# MPU-9250.net
KiCad netlist of a schematic drawn in Altium Designer
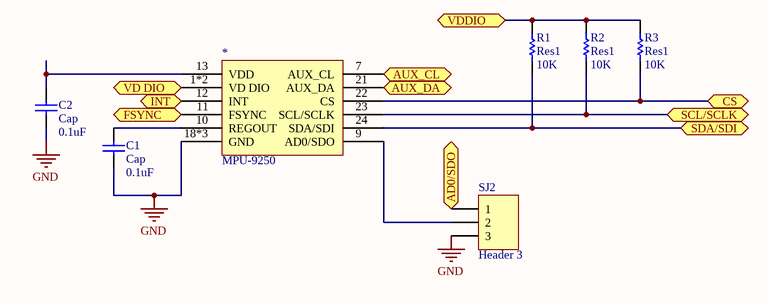
[diagram p0: MPU-9250.SchDoc]

(export (version "E")
  (design (tool "Eeschema 10.0.6"))
  (components
    (comp (ref "*") (value "MPU-9250") (libsource (lib "MPU-9250") (part "Component_1")))
    (comp (ref "C1")
      (value "Cap")
      (footprint "RAD-0.3")
      (description "Capacitor")
      (fields (field (name "ALTIUM_VALUE") "0.1uF") (field (name "PUBLISHER") "Altium Limited"))
      (libsource (lib "Miscellaneous Devices") (part "Cap"))
    )
    (comp (ref "C2")
      (value "Cap")
      (footprint "RAD-0.3")
      (description "Capacitor")
      (fields (field (name "ALTIUM_VALUE") "0.1uF") (field (name "PUBLISHER") "Altium Limited"))
      (libsource (lib "Miscellaneous Devices") (part "Cap"))
    )
    (comp (ref "R1")
      (value "Res1")
      (footprint "AXIAL-0.3")
      (description "Resistor")
      (fields (field (name "ALTIUM_VALUE") "10K") (field (name "PUBLISHER") "Altium Limited"))
      (libsource (lib "Miscellaneous Devices") (part "Res1"))
    )
    (comp (ref "R2")
      (value "Res1")
      (footprint "AXIAL-0.3")
      (description "Resistor")
      (fields (field (name "ALTIUM_VALUE") "10K") (field (name "PUBLISHER") "Altium Limited"))
      (libsource (lib "Miscellaneous Devices") (part "Res1"))
    )
    (comp (ref "R3")
      (value "Res1")
      (footprint "AXIAL-0.3")
      (description "Resistor")
      (fields (field (name "ALTIUM_VALUE") "10K") (field (name "PUBLISHER") "Altium Limited"))
      (libsource (lib "Miscellaneous Devices") (part "Res1"))
    )
    (comp (ref "SJ2")
      (value "Header 3")
      (footprint "HDR1X3")
      (description "Header, 3-Pin")
      (fields (field (name "PUBLISHER") "Altium Limited"))
      (libsource (lib "Miscellaneous Connectors") (part "Header 3"))
    )
  )
  (nets
    (net (code "1") (name "/AD0{slash}SDO") (class "Default")
      (node (ref "SJ2") (pin "1") (pinfunction "1_1") (pintype "passive"))
    )
    (net (code "2") (name "/AUX_CL") (class "Default")
      (node (ref "*") (pin "7") (pinfunction "AUX_CL_7") (pintype "passive"))
    )
    (net (code "3") (name "/AUX_DA") (class "Default")
      (node (ref "*") (pin "21") (pinfunction "AUX_DA_21") (pintype "passive"))
    )
    (net (code "4") (name "/CS") (class "Default")
      (node (ref "*") (pin "22") (pinfunction "CS_22") (pintype "passive"))
      (node (ref "R3") (pin "1") (pinfunction "1_1") (pintype "passive"))
    )
    (net (code "5") (name "/FSYNC") (class "Default")
      (node (ref "*") (pin "11") (pinfunction "FSYNC_11") (pintype "passive"))
    )
    (net (code "6") (name "/INT") (class "Default")
      (node (ref "*") (pin "12") (pinfunction "INT_12") (pintype "passive"))
    )
    (net (code "7") (name "/SCL{slash}SCLK") (class "Default")
      (node (ref "*") (pin "23") (pinfunction "SCL/SCLK_23") (pintype "passive"))
      (node (ref "R2") (pin "1") (pinfunction "1_1") (pintype "passive"))
    )
    (net (code "8") (name "/SDA{slash}SDI") (class "Default")
      (node (ref "*") (pin "24") (pinfunction "SDA/SDI_24") (pintype "passive"))
      (node (ref "R1") (pin "1") (pinfunction "1_1") (pintype "passive"))
    )
    (net (code "9") (name "/VD DIO") (class "Default")
      (node (ref "*") (pin "1*2") (pinfunction "VD_DIO_1*2") (pintype "passive"))
    )
    (net (code "10") (name "/VDDIO") (class "Default")
      (node (ref "R1") (pin "2") (pinfunction "2_2") (pintype "passive"))
      (node (ref "R2") (pin "2") (pinfunction "2_2") (pintype "passive"))
      (node (ref "R3") (pin "2") (pinfunction "2_2") (pintype "passive"))
    )
    (net (code "11") (name "GND") (class "Default")
      (node (ref "*") (pin "18*3") (pinfunction "GND_18*3") (pintype "passive"))
      (node (ref "C1") (pin "1") (pinfunction "1_1") (pintype "passive"))
      (node (ref "C2") (pin "1") (pinfunction "1_1") (pintype "passive"))
      (node (ref "SJ2") (pin "3") (pinfunction "3_3") (pintype "passive"))
    )
    (net (code "12") (name "Net-(*-AD0{slash}SDO)") (class "Default")
      (node (ref "*") (pin "9") (pinfunction "AD0/SDO_9") (pintype "passive"))
      (node (ref "SJ2") (pin "2") (pinfunction "2_2") (pintype "passive"))
    )
    (net (code "13") (name "Net-(*-REGOUT)") (class "Default")
      (node (ref "*") (pin "10") (pinfunction "REGOUT_10") (pintype "passive"))
      (node (ref "C1") (pin "2") (pinfunction "2_2") (pintype "passive"))
    )
    (net (code "14") (name "Net-(*-VDD)") (class "Default")
      (node (ref "*") (pin "13") (pinfunction "VDD_13") (pintype "passive"))
      (node (ref "C2") (pin "2") (pinfunction "2_2") (pintype "passive"))
    )
  )
)
